# AEMBLINK-R1.net
KiCad netlist of a schematic drawn in EAGLE
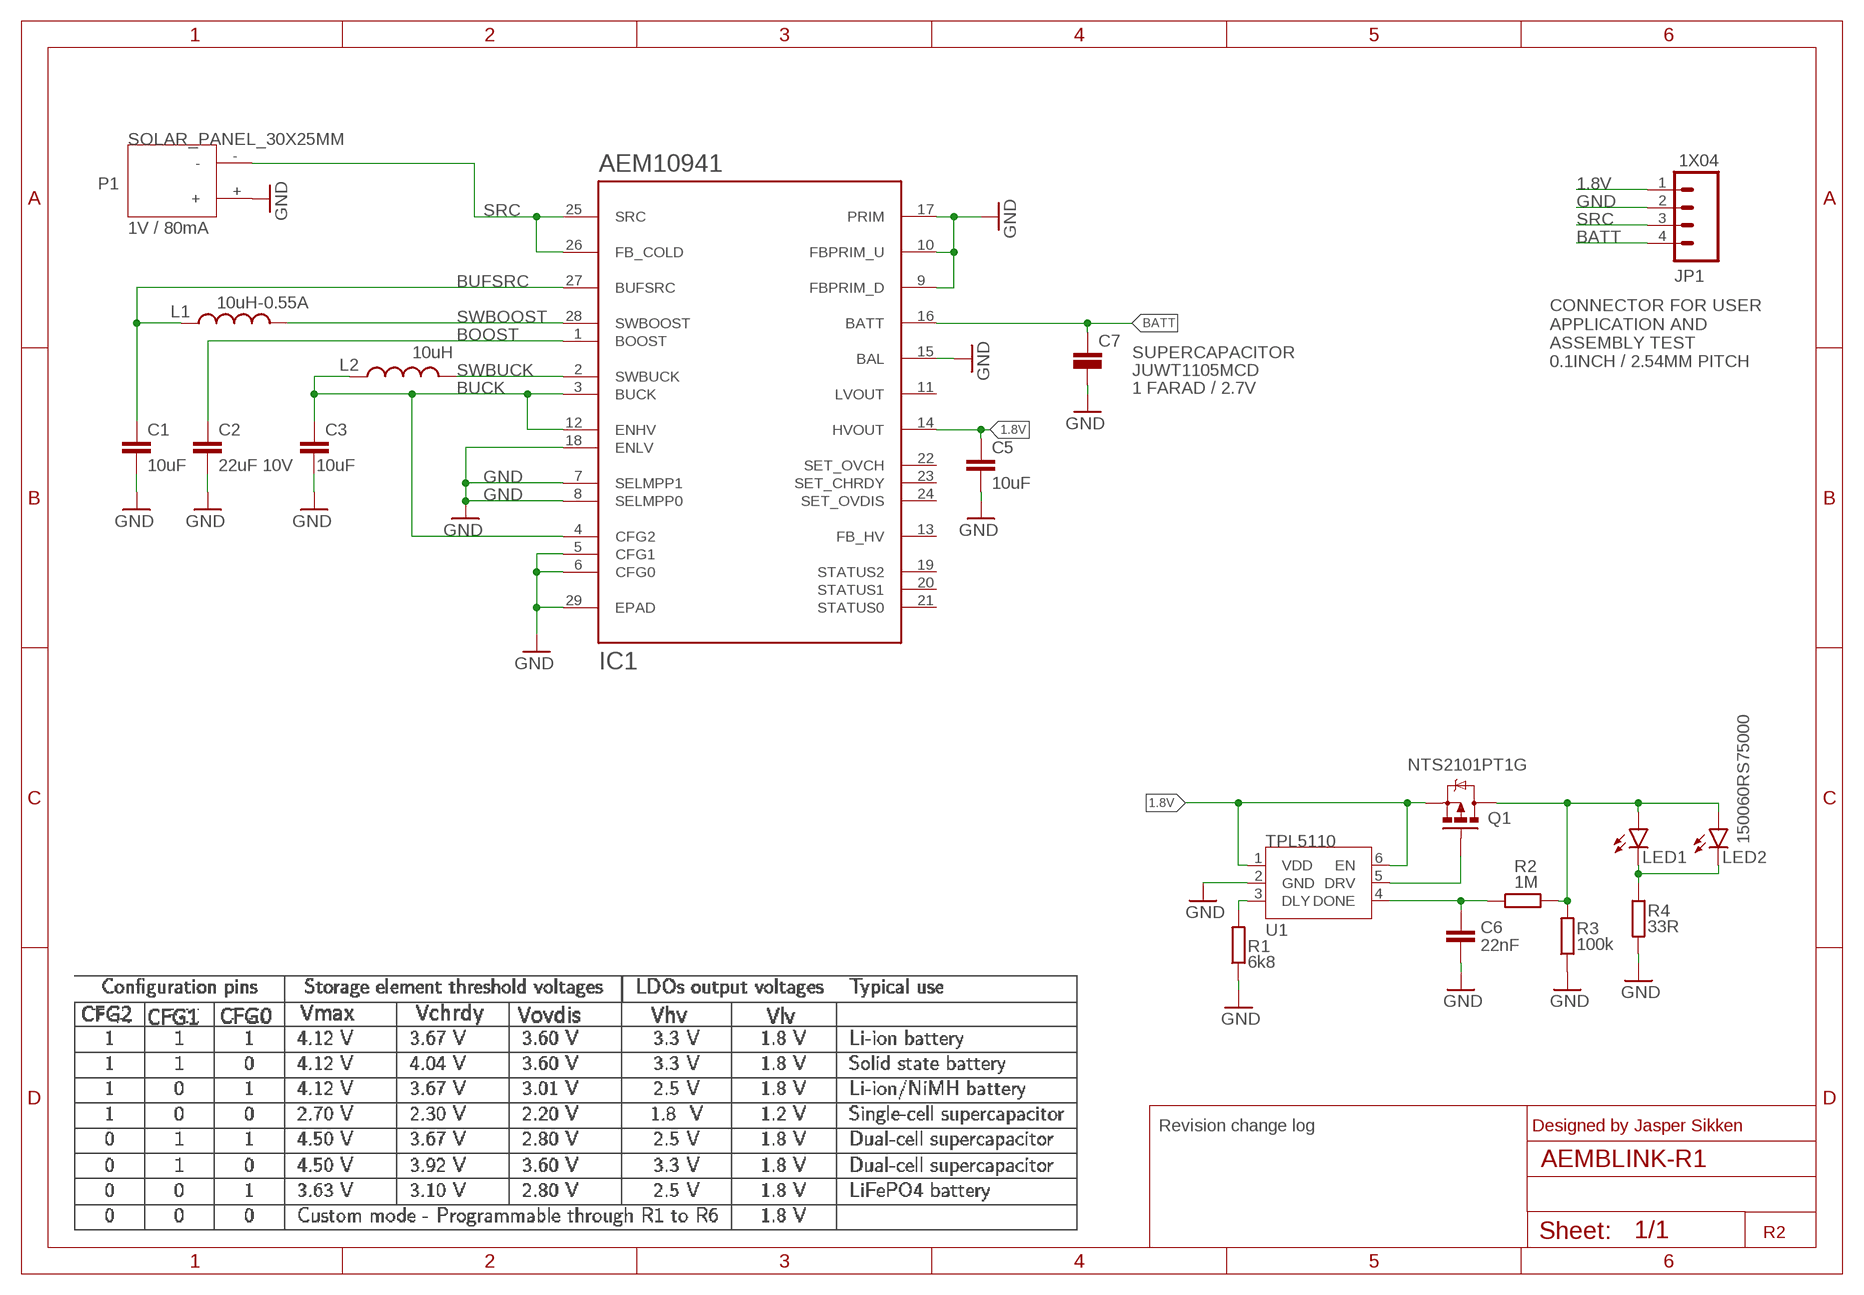
[diagram p0: schematic, sheet 1]

(export (version "E")
  (design (tool "Eeschema 10.0.6"))
  (components
    (comp (ref "C1")
      (value "10uF")
      (footprint "eagle-import:C0603")
      (fields (field (name "MF") "Taiyo Yuden") (field (name "MPN") "LMK107BBJ106MALT"))
      (libsource (lib "eagle-import") (part "C0603_10UF"))
    )
    (comp (ref "C2")
      (value "22uF 10V")
      (footprint "eagle-import:C0603")
      (fields (field (name "MF") "Murata") (field (name "MPN") "GRM188R61A226ME15D"))
      (libsource (lib "eagle-import") (part "C0603_22UF"))
    )
    (comp (ref "C3")
      (value "10uF")
      (footprint "eagle-import:C0603")
      (fields (field (name "MF") "Taiyo Yuden") (field (name "MPN") "LMK107BBJ106MALT"))
      (libsource (lib "eagle-import") (part "C0603_10UF"))
    )
    (comp (ref "C5")
      (value "10uF")
      (footprint "eagle-import:C0603")
      (fields (field (name "MF") "Taiyo Yuden") (field (name "MPN") "LMK107BBJ106MALT"))
      (libsource (lib "eagle-import") (part "C0603_10UF"))
    )
    (comp (ref "C6")
      (value "22nF")
      (footprint "eagle-import:C0603")
      (libsource (lib "eagle-import") (part "C0603_10NF"))
    )
    (comp (ref "C7")
      (value "JUWT1105MCD")
      (footprint "eagle-import:C_RADIAL_9L6.3D2.5P0.5H_HOR")
      (libsource (lib "eagle-import") (part "SUPERCAPNICHICON"))
    )
    (comp (ref "IC1")
      (value "AEM10941")
      (footprint "eagle-import:QFN50P505X505X90-28")
      (fields (field (name "MF") "e-peas"))
      (libsource (lib "eagle-import") (part "AEM10941"))
    )
    (comp (ref "JP1")
      (value "1X04")
      (footprint "eagle-import:1X04_2.54MM_ROUND_NOSILK")
      (libsource (lib "eagle-import") (part "1X04"))
    )
    (comp (ref "L1")
      (value "10uH-0.55A")
      (footprint "eagle-import:LPS4012")
      (fields (field (name "MF") "Coilcraft") (field (name "MPN") "LPS4012-103MRB"))
      (libsource (lib "eagle-import") (part "L3.9X3.9_10UH_0.55A"))
    )
    (comp (ref "L2")
      (value "10uH")
      (footprint "eagle-import:L0603")
      (fields (field (name "MF") "TDK") (field (name "MPN") "MLZ1608M100WT"))
      (libsource (lib "eagle-import") (part "L0603_10UH"))
    )
    (comp (ref "LED1")
      (value "LEDCHIPLED_0603")
      (footprint "eagle-import:CHIPLED_0603")
      (libsource (lib "eagle-import") (part "LEDCHIPLED_0603"))
    )
    (comp (ref "LED2")
      (value "150060RS75000")
      (footprint "eagle-import:CHIPLED_0603")
      (libsource (lib "eagle-import") (part "LEDCHIPLED_0603"))
    )
    (comp (ref "P1")
      (value "SOLAR_PANEL_30X25MM")
      (footprint "eagle-import:SOLAR_PANEL_30X25")
      (libsource (lib "eagle-import") (part "SOLAR_PANEL_30X25MM"))
    )
    (comp (ref "Q1")
      (value "NTS2101PT1G")
      (footprint "eagle-import:SOT323")
      (libsource (lib "eagle-import") (part "MOSFET-P-CHANNEL-DMP2160UW"))
    )
    (comp (ref "R1")
      (value "6k8")
      (footprint "eagle-import:R0603")
      (libsource (lib "eagle-import") (part "R-EU_R0603"))
    )
    (comp (ref "R2")
      (value "1M")
      (footprint "eagle-import:R0603")
      (libsource (lib "eagle-import") (part "R0603_1M"))
    )
    (comp (ref "R3")
      (value "100k")
      (footprint "eagle-import:R0603")
      (libsource (lib "eagle-import") (part "R0603_1M"))
    )
    (comp (ref "R4")
      (value "33R")
      (footprint "eagle-import:R0603")
      (libsource (lib "eagle-import") (part "R-EU_R0603"))
    )
    (comp (ref "U1")
      (value "TPL5110")
      (footprint "eagle-import:SOT23-6")
      (libsource (lib "eagle-import") (part "TPL5110"))
    )
  )
  (nets
    (net (code "1") (name "/BOOST") (class "Default")
      (node (ref "C2") (pin "1") (pinfunction "1_1") (pintype "passive"))
      (node (ref "IC1") (pin "1") (pinfunction "BOOST_1") (pintype "bidirectional"))
    )
    (net (code "2") (name "/BUCK") (class "Default")
      (node (ref "C3") (pin "1") (pinfunction "1_1") (pintype "passive"))
      (node (ref "IC1") (pin "12") (pinfunction "ENHV_12") (pintype "bidirectional"))
      (node (ref "IC1") (pin "3") (pinfunction "BUCK_3") (pintype "bidirectional"))
      (node (ref "IC1") (pin "4") (pinfunction "CFG2_4") (pintype "bidirectional"))
      (node (ref "L2") (pin "1") (pinfunction "1_1") (pintype "passive"))
    )
    (net (code "3") (name "/BUFSRC") (class "Default")
      (node (ref "C1") (pin "1") (pinfunction "1_1") (pintype "passive"))
      (node (ref "IC1") (pin "27") (pinfunction "BUFSRC_27") (pintype "power_in"))
      (node (ref "L1") (pin "1") (pinfunction "1_1") (pintype "passive"))
    )
    (net (code "4") (name "/SRC") (class "Default")
      (node (ref "IC1") (pin "25") (pinfunction "SRC_25") (pintype "power_in"))
      (node (ref "IC1") (pin "26") (pinfunction "FB_COLD_26") (pintype "input"))
      (node (ref "JP1") (pin "3") (pinfunction "3_3") (pintype "passive"))
      (node (ref "P1") (pin "-") (pinfunction "-_-") (pintype "bidirectional"))
    )
    (net (code "5") (name "/SWBOOST") (class "Default")
      (node (ref "IC1") (pin "28") (pinfunction "SWBOOST_28") (pintype "power_in"))
      (node (ref "L1") (pin "2") (pinfunction "2_2") (pintype "passive"))
    )
    (net (code "6") (name "/SWBUCK") (class "Default")
      (node (ref "IC1") (pin "2") (pinfunction "SWBUCK_2") (pintype "bidirectional"))
      (node (ref "L2") (pin "2") (pinfunction "2_2") (pintype "passive"))
    )
    (net (code "7") (name "1.8V") (class "Default")
      (node (ref "C5") (pin "1") (pinfunction "1_1") (pintype "passive"))
      (node (ref "IC1") (pin "14") (pinfunction "HVOUT_14") (pintype "bidirectional"))
      (node (ref "JP1") (pin "1") (pinfunction "1_1") (pintype "passive"))
      (node (ref "Q1") (pin "2") (pinfunction "S_2") (pintype "passive"))
      (node (ref "U1") (pin "1") (pinfunction "VDD_1") (pintype "bidirectional"))
      (node (ref "U1") (pin "6") (pinfunction "EN_6") (pintype "bidirectional"))
    )
    (net (code "8") (name "BATT") (class "Default")
      (node (ref "C7") (pin "+") (pinfunction "+_+") (pintype "passive"))
      (node (ref "IC1") (pin "16") (pinfunction "BATT_16") (pintype "bidirectional"))
      (node (ref "JP1") (pin "4") (pinfunction "4_4") (pintype "passive"))
    )
    (net (code "9") (name "GND") (class "Default")
      (node (ref "C1") (pin "2") (pinfunction "2_2") (pintype "passive"))
      (node (ref "C2") (pin "2") (pinfunction "2_2") (pintype "passive"))
      (node (ref "C3") (pin "2") (pinfunction "2_2") (pintype "passive"))
      (node (ref "C5") (pin "2") (pinfunction "2_2") (pintype "passive"))
      (node (ref "C6") (pin "2") (pinfunction "2_2") (pintype "passive"))
      (node (ref "C7") (pin "-") (pinfunction "-_-") (pintype "passive"))
      (node (ref "IC1") (pin "10") (pinfunction "FBPRIM_U_10") (pintype "bidirectional"))
      (node (ref "IC1") (pin "15") (pinfunction "BAL_15") (pintype "bidirectional"))
      (node (ref "IC1") (pin "17") (pinfunction "PRIM_17") (pintype "bidirectional"))
      (node (ref "IC1") (pin "18") (pinfunction "ENLV_18") (pintype "bidirectional"))
      (node (ref "IC1") (pin "29") (pinfunction "EPAD_29") (pintype "power_in"))
      (node (ref "IC1") (pin "5") (pinfunction "CFG1_5") (pintype "bidirectional"))
      (node (ref "IC1") (pin "6") (pinfunction "CFG0_6") (pintype "bidirectional"))
      (node (ref "IC1") (pin "7") (pinfunction "SELMPP1_7") (pintype "bidirectional"))
      (node (ref "IC1") (pin "8") (pinfunction "SELMPP0_8") (pintype "bidirectional"))
      (node (ref "IC1") (pin "9") (pinfunction "FBPRIM_D_9") (pintype "bidirectional"))
      (node (ref "JP1") (pin "2") (pinfunction "2_2") (pintype "passive"))
      (node (ref "P1") (pin "+") (pinfunction "+_+") (pintype "bidirectional"))
      (node (ref "R1") (pin "1") (pinfunction "1_1") (pintype "passive"))
      (node (ref "R3") (pin "1") (pinfunction "1_1") (pintype "passive"))
      (node (ref "R4") (pin "2") (pinfunction "2_2") (pintype "passive"))
      (node (ref "U1") (pin "2") (pinfunction "GND_2") (pintype "bidirectional"))
    )
    (net (code "10") (name "Net-(LED1-PadC)") (class "Default")
      (node (ref "LED1") (pin "C") (pinfunction "C_C") (pintype "passive"))
      (node (ref "LED2") (pin "C") (pinfunction "C_C") (pintype "passive"))
      (node (ref "R4") (pin "1") (pinfunction "1_1") (pintype "passive"))
    )
    (net (code "11") (name "Net-(Q1-D)") (class "Default")
      (node (ref "LED1") (pin "A") (pinfunction "A_A") (pintype "passive"))
      (node (ref "LED2") (pin "A") (pinfunction "A_A") (pintype "passive"))
      (node (ref "Q1") (pin "3") (pinfunction "D_3") (pintype "passive"))
      (node (ref "R2") (pin "2") (pinfunction "2_2") (pintype "passive"))
      (node (ref "R3") (pin "2") (pinfunction "2_2") (pintype "passive"))
    )
    (net (code "12") (name "Net-(Q1-G)") (class "Default")
      (node (ref "Q1") (pin "1") (pinfunction "G_1") (pintype "passive"))
      (node (ref "U1") (pin "5") (pinfunction "DRV_5") (pintype "bidirectional"))
    )
    (net (code "13") (name "Net-(U1-DLY)") (class "Default")
      (node (ref "R1") (pin "2") (pinfunction "2_2") (pintype "passive"))
      (node (ref "U1") (pin "3") (pinfunction "DLY_3") (pintype "bidirectional"))
    )
    (net (code "14") (name "Net-(U1-DONE)") (class "Default")
      (node (ref "C6") (pin "1") (pinfunction "1_1") (pintype "passive"))
      (node (ref "R2") (pin "1") (pinfunction "1_1") (pintype "passive"))
      (node (ref "U1") (pin "4") (pinfunction "DONE_4") (pintype "bidirectional"))
    )
    (net (code "15") (name "unconnected-(IC1-FB_HV-Pad13)") (class "Default")
      (node (ref "IC1") (pin "13") (pinfunction "FB_HV_13") (pintype "bidirectional"))
    )
    (net (code "16") (name "unconnected-(IC1-LVOUT-Pad11)") (class "Default")
      (node (ref "IC1") (pin "11") (pinfunction "LVOUT_11") (pintype "bidirectional"))
    )
    (net (code "17") (name "unconnected-(IC1-SET_CHRDY-Pad23)") (class "Default")
      (node (ref "IC1") (pin "23") (pinfunction "SET_CHRDY_23") (pintype "bidirectional"))
    )
    (net (code "18") (name "unconnected-(IC1-SET_OVCH-Pad22)") (class "Default")
      (node (ref "IC1") (pin "22") (pinfunction "SET_OVCH_22") (pintype "bidirectional"))
    )
    (net (code "19") (name "unconnected-(IC1-SET_OVDIS-Pad24)") (class "Default")
      (node (ref "IC1") (pin "24") (pinfunction "SET_OVDIS_24") (pintype "bidirectional"))
    )
    (net (code "20") (name "unconnected-(IC1-STATUS0-Pad21)") (class "Default")
      (node (ref "IC1") (pin "21") (pinfunction "STATUS0_21") (pintype "bidirectional"))
    )
    (net (code "21") (name "unconnected-(IC1-STATUS1-Pad20)") (class "Default")
      (node (ref "IC1") (pin "20") (pinfunction "STATUS1_20") (pintype "bidirectional"))
    )
    (net (code "22") (name "unconnected-(IC1-STATUS2-Pad19)") (class "Default")
      (node (ref "IC1") (pin "19") (pinfunction "STATUS2_19") (pintype "bidirectional"))
    )
  )
)
